# Sheet1.net
KiCad netlist of a schematic drawn in Altium Designer
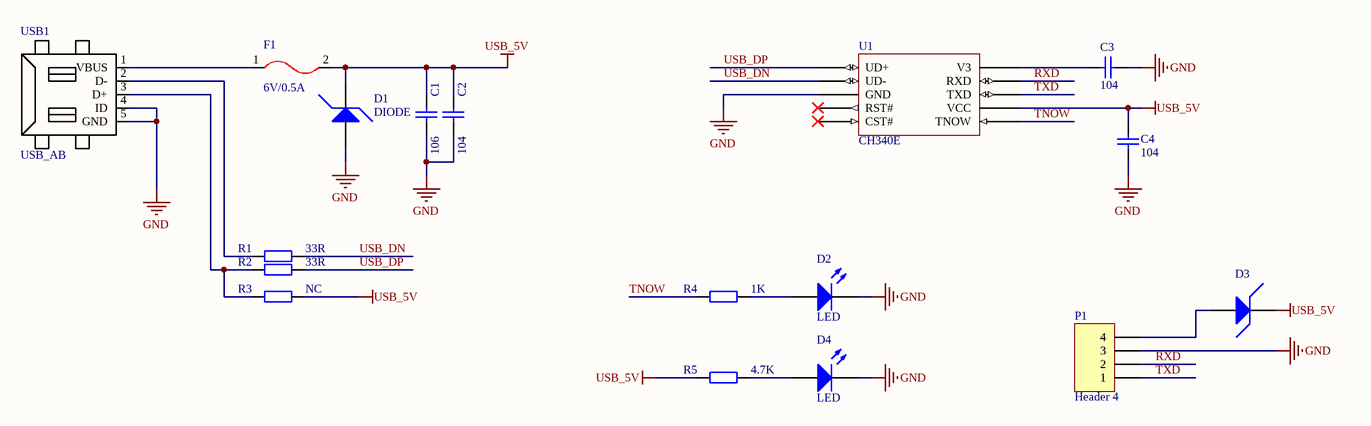
[diagram p0: Sheet1.SchDoc]

(export (version "E")
  (design (tool "Eeschema 10.0.6"))
  (components
    (comp (ref "C1") (value "106") (footprint "C_SOP_0603") (libsource (lib "DG") (part "C_SMD")))
    (comp (ref "C2") (value "104") (footprint "C_SOP_0603") (libsource (lib "DG") (part "C_SMD")))
    (comp (ref "C3") (value "104") (footprint "C_SOP_0603") (libsource (lib "DG") (part "C_SMD")))
    (comp (ref "C4") (value "104") (footprint "C_SOP_0603") (libsource (lib "DG") (part "C_SMD")))
    (comp (ref "D1") (value "DIODE") (footprint "SOD-523") (libsource (lib "DG") (part "DIODE")))
    (comp (ref "D2") (value "LED") (footprint "LED_0603_R") (libsource (lib "DG") (part "LED")))
    (comp (ref "D3") (value "~") (footprint "SOD-523") (libsource (lib "DG") (part "DIODE")))
    (comp (ref "D4") (value "LED") (footprint "LED_0603_R") (libsource (lib "DG") (part "LED")))
    (comp (ref "F1") (value "6V/0.5A") (footprint "Fuse_0805") (libsource (lib "DG") (part "FUSE")))
    (comp (ref "P1")
      (value "Header 4")
      (footprint "HDR1X4")
      (description "Header, 4-Pin")
      (fields (field (name "PUBLISHER") "Altium Limited"))
      (libsource (lib "Miscellaneous Connectors") (part "Header 4"))
    )
    (comp (ref "R1") (value "33R") (footprint "R_SMD_0603") (libsource (lib "DG") (part "R_SMD")))
    (comp (ref "R2") (value "33R") (footprint "R_SMD_0603") (libsource (lib "DG") (part "R_SMD")))
    (comp (ref "R3") (value "NC") (footprint "R_SMD_0603") (libsource (lib "DG") (part "R_SMD")))
    (comp (ref "R4") (value "1K") (footprint "R_SMD_0603") (libsource (lib "DG") (part "R_SMD")))
    (comp (ref "R5") (value "4.7K") (footprint "R_SMD_0603") (libsource (lib "DG") (part "R_SMD")))
    (comp (ref "U1") (value "CH340E") (footprint "MSOP_10") (libsource (lib "DG") (part "CH340E")))
    (comp (ref "USB1") (value "USB_AB") (footprint "USB_MINI_SMD") (libsource (lib "DG") (part "USB_AB")))
  )
  (nets
    (net (code "1") (name "/RXD") (class "Default")
      (node (ref "P1") (pin "2") (pinfunction "2_2") (pintype "passive"))
      (node (ref "U1") (pin "9") (pinfunction "RXD_9") (pintype "bidirectional"))
    )
    (net (code "2") (name "/TNOW") (class "Default")
      (node (ref "R4") (pin "1") (pinfunction "1_1") (pintype "passive"))
      (node (ref "U1") (pin "6") (pinfunction "TNOW_6") (pintype "input"))
    )
    (net (code "3") (name "/TXD") (class "Default")
      (node (ref "P1") (pin "1") (pinfunction "1_1") (pintype "passive"))
      (node (ref "U1") (pin "8") (pinfunction "TXD_8") (pintype "bidirectional"))
    )
    (net (code "4") (name "/USB_DN") (class "Default")
      (node (ref "R1") (pin "2") (pinfunction "2_2") (pintype "passive"))
      (node (ref "U1") (pin "2") (pinfunction "UD-_2") (pintype "bidirectional"))
    )
    (net (code "5") (name "/USB_DP") (class "Default")
      (node (ref "R2") (pin "2") (pinfunction "2_2") (pintype "passive"))
      (node (ref "U1") (pin "1") (pinfunction "UD+_1") (pintype "bidirectional"))
    )
    (net (code "6") (name "GND") (class "Default")
      (node (ref "C1") (pin "1") (pinfunction "1_1") (pintype "passive"))
      (node (ref "C2") (pin "1") (pinfunction "1_1") (pintype "passive"))
      (node (ref "C3") (pin "1") (pinfunction "1_1") (pintype "passive"))
      (node (ref "C4") (pin "2") (pinfunction "2_2") (pintype "passive"))
      (node (ref "D1") (pin "2") (pinfunction "A_2") (pintype "passive"))
      (node (ref "D2") (pin "2") (pinfunction "K_2") (pintype "passive"))
      (node (ref "D4") (pin "2") (pinfunction "K_2") (pintype "passive"))
      (node (ref "P1") (pin "3") (pinfunction "3_3") (pintype "passive"))
      (node (ref "U1") (pin "3") (pinfunction "GND_3") (pintype "power_in"))
      (node (ref "USB1") (pin "4") (pinfunction "ID_4") (pintype "passive"))
      (node (ref "USB1") (pin "5") (pinfunction "GND_5") (pintype "passive"))
    )
    (net (code "7") (name "Net-(D2-A)") (class "Default")
      (node (ref "D2") (pin "1") (pinfunction "A_1") (pintype "passive"))
      (node (ref "R4") (pin "2") (pinfunction "2_2") (pintype "passive"))
    )
    (net (code "8") (name "Net-(D3-A)") (class "Default")
      (node (ref "D3") (pin "2") (pinfunction "A_2") (pintype "passive"))
      (node (ref "P1") (pin "4") (pinfunction "4_4") (pintype "passive"))
    )
    (net (code "9") (name "Net-(D4-A)") (class "Default")
      (node (ref "D4") (pin "1") (pinfunction "A_1") (pintype "passive"))
      (node (ref "R5") (pin "2") (pinfunction "2_2") (pintype "passive"))
    )
    (net (code "10") (name "Net-(U1-V3)") (class "Default")
      (node (ref "C3") (pin "2") (pinfunction "2_2") (pintype "passive"))
      (node (ref "U1") (pin "10") (pinfunction "V3_10") (pintype "power_in"))
    )
    (net (code "11") (name "Net-(USB1-D+)") (class "Default")
      (node (ref "R2") (pin "1") (pinfunction "1_1") (pintype "passive"))
      (node (ref "R3") (pin "1") (pinfunction "1_1") (pintype "passive"))
      (node (ref "USB1") (pin "3") (pinfunction "D+_3") (pintype "passive"))
    )
    (net (code "12") (name "Net-(USB1-D-)") (class "Default")
      (node (ref "R1") (pin "1") (pinfunction "1_1") (pintype "passive"))
      (node (ref "USB1") (pin "2") (pinfunction "D-_2") (pintype "passive"))
    )
    (net (code "13") (name "Net-(USB1-VBUS)") (class "Default")
      (node (ref "F1") (pin "1") (pinfunction "OUT_1") (pintype "passive"))
      (node (ref "USB1") (pin "1") (pinfunction "VBUS_1") (pintype "passive"))
    )
    (net (code "14") (name "USB_5V") (class "Default")
      (node (ref "C1") (pin "2") (pinfunction "2_2") (pintype "passive"))
      (node (ref "C2") (pin "2") (pinfunction "2_2") (pintype "passive"))
      (node (ref "C4") (pin "1") (pinfunction "1_1") (pintype "passive"))
      (node (ref "D1") (pin "1") (pinfunction "K_1") (pintype "passive"))
      (node (ref "D3") (pin "1") (pinfunction "K_1") (pintype "passive"))
      (node (ref "F1") (pin "2") (pinfunction "OUT_2") (pintype "passive"))
      (node (ref "R3") (pin "2") (pinfunction "2_2") (pintype "passive"))
      (node (ref "R5") (pin "1") (pinfunction "1_1") (pintype "passive"))
      (node (ref "U1") (pin "7") (pinfunction "VCC_7") (pintype "power_in"))
    )
    (net (code "15") (name "unconnected-(U1-CST#-Pad5)") (class "Default")
      (node (ref "U1") (pin "5") (pinfunction "CST#_5") (pintype "input+no_connect"))
    )
    (net (code "16") (name "unconnected-(U1-RST#-Pad4)") (class "Default")
      (node (ref "U1") (pin "4") (pinfunction "RST#_4") (pintype "output+no_connect"))
    )
  )
)
